# takiuino-m18-routed-smashed.net
KiCad netlist of a schematic drawn in EAGLE
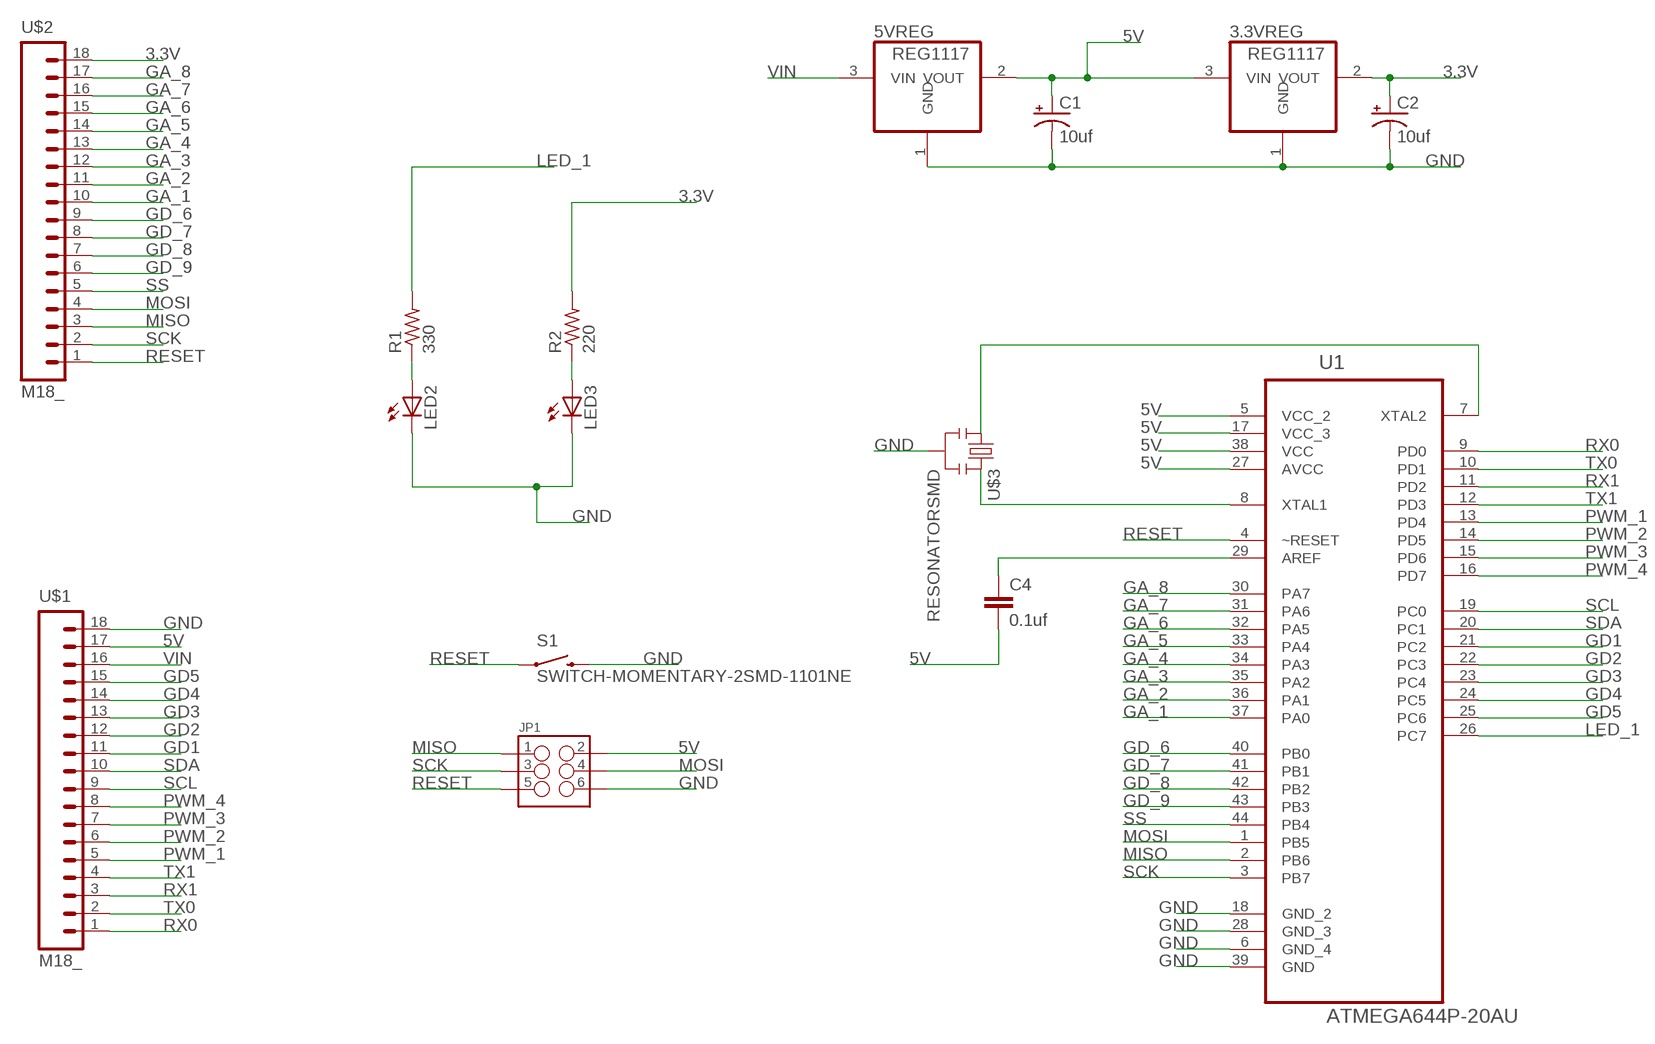
[diagram p0: schematic, sheet 1]

(export (version "E")
  (design (tool "Eeschema 10.0.6"))
  (components
    (comp (ref "3.3VREG")
      (value "REG1117")
      (footprint "eagle-import:SOT223")
      (libsource (lib "eagle-import") (part "REG1117"))
    )
    (comp (ref "5VREG")
      (value "REG1117")
      (footprint "eagle-import:SOT223")
      (libsource (lib "eagle-import") (part "REG1117"))
    )
    (comp (ref "C1")
      (value "10uf")
      (footprint "eagle-import:EIA3216")
      (libsource (lib "eagle-import") (part "CAP_POL1206"))
    )
    (comp (ref "C2")
      (value "10uf")
      (footprint "eagle-import:EIA3216")
      (libsource (lib "eagle-import") (part "CAP_POL1206"))
    )
    (comp (ref "C4")
      (value "0.1uf")
      (footprint "eagle-import:0603-CAP")
      (libsource (lib "eagle-import") (part "CAP0603-CAP"))
    )
    (comp (ref "JP1")
      (value "M03X2NO_SILK")
      (footprint "eagle-import:2X3-NS")
      (libsource (lib "eagle-import") (part "M03X2NO_SILK"))
    )
    (comp (ref "LED2")
      (value "LEDCHIP-LED0603")
      (footprint "eagle-import:CHIP-LED0603")
      (libsource (lib "eagle-import") (part "LEDCHIP-LED0603"))
    )
    (comp (ref "LED3")
      (value "LEDCHIP-LED0603")
      (footprint "eagle-import:CHIP-LED0603")
      (libsource (lib "eagle-import") (part "LEDCHIP-LED0603"))
    )
    (comp (ref "R1")
      (value "330")
      (footprint "eagle-import:R0603")
      (libsource (lib "eagle-import") (part "R-US_R0603"))
    )
    (comp (ref "R2")
      (value "220")
      (footprint "eagle-import:R0603")
      (libsource (lib "eagle-import") (part "R-US_R0603"))
    )
    (comp (ref "S1")
      (value "SWITCH-MOMENTARY-2SMD-1101NE")
      (footprint "eagle-import:TACTILE-SWITCH-1101NE")
      (libsource (lib "eagle-import") (part "SWITCH-MOMENTARY-2SMD-1101NE"))
    )
    (comp (ref "U$1")
      (value "M18_")
      (footprint "eagle-import:1X18")
      (libsource (lib "eagle-import") (part "M18_"))
    )
    (comp (ref "U$2")
      (value "M18_")
      (footprint "eagle-import:1X18")
      (libsource (lib "eagle-import") (part "M18_"))
    )
    (comp (ref "U$3")
      (value "RESONATORSMD")
      (footprint "eagle-import:RESONATOR-SMD")
      (libsource (lib "eagle-import") (part "RESONATORSMD"))
    )
    (comp (ref "U1")
      (value "ATMEGA644P-20AU")
      (footprint "eagle-import:QFP80P1200X1200X120-44N")
      (libsource (lib "eagle-import") (part "ATMEGA644P-20AU"))
    )
  )
  (nets
    (net (code "1") (name "/3.3V") (class "Default")
      (node (ref "3.3VREG") (pin "2") (pinfunction "VOUT_2") (pintype "output"))
      (node (ref "C2") (pin "A") (pinfunction "+_A") (pintype "passive"))
      (node (ref "R2") (pin "2") (pinfunction "2_2") (pintype "passive"))
      (node (ref "U$2") (pin "18") (pinfunction "18_18") (pintype "passive"))
    )
    (net (code "2") (name "/5V") (class "Default")
      (node (ref "3.3VREG") (pin "3") (pinfunction "VIN_3") (pintype "input"))
      (node (ref "5VREG") (pin "2") (pinfunction "VOUT_2") (pintype "output"))
      (node (ref "C1") (pin "A") (pinfunction "+_A") (pintype "passive"))
      (node (ref "C4") (pin "2") (pinfunction "2_2") (pintype "passive"))
      (node (ref "JP1") (pin "2") (pinfunction "2_2") (pintype "bidirectional"))
      (node (ref "U$1") (pin "17") (pinfunction "17_17") (pintype "passive"))
      (node (ref "U1") (pin "17") (pinfunction "VCC_3_17") (pintype "power_in"))
      (node (ref "U1") (pin "27") (pinfunction "AVCC_27") (pintype "power_in"))
      (node (ref "U1") (pin "38") (pinfunction "VCC_38") (pintype "power_in"))
      (node (ref "U1") (pin "5") (pinfunction "VCC_2_5") (pintype "power_in"))
    )
    (net (code "3") (name "/GA_1") (class "Default")
      (node (ref "U$2") (pin "10") (pinfunction "10_10") (pintype "passive"))
      (node (ref "U1") (pin "37") (pinfunction "PA0_37") (pintype "bidirectional"))
    )
    (net (code "4") (name "/GA_2") (class "Default")
      (node (ref "U$2") (pin "11") (pinfunction "11_11") (pintype "passive"))
      (node (ref "U1") (pin "36") (pinfunction "PA1_36") (pintype "bidirectional"))
    )
    (net (code "5") (name "/GA_3") (class "Default")
      (node (ref "U$2") (pin "12") (pinfunction "12_12") (pintype "passive"))
      (node (ref "U1") (pin "35") (pinfunction "PA2_35") (pintype "bidirectional"))
    )
    (net (code "6") (name "/GA_4") (class "Default")
      (node (ref "U$2") (pin "13") (pinfunction "13_13") (pintype "passive"))
      (node (ref "U1") (pin "34") (pinfunction "PA3_34") (pintype "bidirectional"))
    )
    (net (code "7") (name "/GA_5") (class "Default")
      (node (ref "U$2") (pin "14") (pinfunction "14_14") (pintype "passive"))
      (node (ref "U1") (pin "33") (pinfunction "PA4_33") (pintype "bidirectional"))
    )
    (net (code "8") (name "/GA_6") (class "Default")
      (node (ref "U$2") (pin "15") (pinfunction "15_15") (pintype "passive"))
      (node (ref "U1") (pin "32") (pinfunction "PA5_32") (pintype "bidirectional"))
    )
    (net (code "9") (name "/GA_7") (class "Default")
      (node (ref "U$2") (pin "16") (pinfunction "16_16") (pintype "passive"))
      (node (ref "U1") (pin "31") (pinfunction "PA6_31") (pintype "bidirectional"))
    )
    (net (code "10") (name "/GA_8") (class "Default")
      (node (ref "U$2") (pin "17") (pinfunction "17_17") (pintype "passive"))
      (node (ref "U1") (pin "30") (pinfunction "PA7_30") (pintype "bidirectional"))
    )
    (net (code "11") (name "/GD1") (class "Default")
      (node (ref "U$1") (pin "11") (pinfunction "11_11") (pintype "passive"))
      (node (ref "U1") (pin "21") (pinfunction "PC2_21") (pintype "bidirectional"))
    )
    (net (code "12") (name "/GD2") (class "Default")
      (node (ref "U$1") (pin "12") (pinfunction "12_12") (pintype "passive"))
      (node (ref "U1") (pin "22") (pinfunction "PC3_22") (pintype "bidirectional"))
    )
    (net (code "13") (name "/GD3") (class "Default")
      (node (ref "U$1") (pin "13") (pinfunction "13_13") (pintype "passive"))
      (node (ref "U1") (pin "23") (pinfunction "PC4_23") (pintype "bidirectional"))
    )
    (net (code "14") (name "/GD4") (class "Default")
      (node (ref "U$1") (pin "14") (pinfunction "14_14") (pintype "passive"))
      (node (ref "U1") (pin "24") (pinfunction "PC5_24") (pintype "bidirectional"))
    )
    (net (code "15") (name "/GD5") (class "Default")
      (node (ref "U$1") (pin "15") (pinfunction "15_15") (pintype "passive"))
      (node (ref "U1") (pin "25") (pinfunction "PC6_25") (pintype "bidirectional"))
    )
    (net (code "16") (name "/GD_6") (class "Default")
      (node (ref "U$2") (pin "9") (pinfunction "9_9") (pintype "passive"))
      (node (ref "U1") (pin "40") (pinfunction "PB0_40") (pintype "bidirectional"))
    )
    (net (code "17") (name "/GD_7") (class "Default")
      (node (ref "U$2") (pin "8") (pinfunction "8_8") (pintype "passive"))
      (node (ref "U1") (pin "41") (pinfunction "PB1_41") (pintype "bidirectional"))
    )
    (net (code "18") (name "/GD_8") (class "Default")
      (node (ref "U$2") (pin "7") (pinfunction "7_7") (pintype "passive"))
      (node (ref "U1") (pin "42") (pinfunction "PB2_42") (pintype "bidirectional"))
    )
    (net (code "19") (name "/GD_9") (class "Default")
      (node (ref "U$2") (pin "6") (pinfunction "6_6") (pintype "passive"))
      (node (ref "U1") (pin "43") (pinfunction "PB3_43") (pintype "bidirectional"))
    )
    (net (code "20") (name "/GND") (class "Default")
      (node (ref "3.3VREG") (pin "1") (pinfunction "GND_1") (pintype "power_in"))
      (node (ref "5VREG") (pin "1") (pinfunction "GND_1") (pintype "power_in"))
      (node (ref "C1") (pin "C") (pinfunction "-_C") (pintype "passive"))
      (node (ref "C2") (pin "C") (pinfunction "-_C") (pintype "passive"))
      (node (ref "JP1") (pin "6") (pinfunction "6_6") (pintype "bidirectional"))
      (node (ref "LED2") (pin "C") (pinfunction "C_C") (pintype "passive"))
      (node (ref "LED3") (pin "C") (pinfunction "C_C") (pintype "passive"))
      (node (ref "S1") (pin "2") (pinfunction "2_2") (pintype "passive"))
      (node (ref "U$1") (pin "18") (pinfunction "18_18") (pintype "passive"))
      (node (ref "U$3") (pin "2") (pinfunction "2_2") (pintype "passive"))
      (node (ref "U1") (pin "18") (pinfunction "GND_2_18") (pintype "passive"))
      (node (ref "U1") (pin "28") (pinfunction "GND_3_28") (pintype "passive"))
      (node (ref "U1") (pin "39") (pinfunction "GND_39") (pintype "passive"))
      (node (ref "U1") (pin "6") (pinfunction "GND_4_6") (pintype "passive"))
    )
    (net (code "21") (name "/LED_1") (class "Default")
      (node (ref "R1") (pin "2") (pinfunction "2_2") (pintype "passive"))
      (node (ref "U1") (pin "26") (pinfunction "PC7_26") (pintype "bidirectional"))
    )
    (net (code "22") (name "/MISO") (class "Default")
      (node (ref "JP1") (pin "1") (pinfunction "1_1") (pintype "bidirectional"))
      (node (ref "U$2") (pin "3") (pinfunction "3_3") (pintype "passive"))
      (node (ref "U1") (pin "2") (pinfunction "PB6_2") (pintype "bidirectional"))
    )
    (net (code "23") (name "/MOSI") (class "Default")
      (node (ref "JP1") (pin "4") (pinfunction "4_4") (pintype "bidirectional"))
      (node (ref "U$2") (pin "4") (pinfunction "4_4") (pintype "passive"))
      (node (ref "U1") (pin "1") (pinfunction "PB5_1") (pintype "bidirectional"))
    )
    (net (code "24") (name "/PWM_1") (class "Default")
      (node (ref "U$1") (pin "5") (pinfunction "5_5") (pintype "passive"))
      (node (ref "U1") (pin "13") (pinfunction "PD4_13") (pintype "bidirectional"))
    )
    (net (code "25") (name "/PWM_2") (class "Default")
      (node (ref "U$1") (pin "6") (pinfunction "6_6") (pintype "passive"))
      (node (ref "U1") (pin "14") (pinfunction "PD5_14") (pintype "bidirectional"))
    )
    (net (code "26") (name "/PWM_3") (class "Default")
      (node (ref "U$1") (pin "7") (pinfunction "7_7") (pintype "passive"))
      (node (ref "U1") (pin "15") (pinfunction "PD6_15") (pintype "bidirectional"))
    )
    (net (code "27") (name "/PWM_4") (class "Default")
      (node (ref "U$1") (pin "8") (pinfunction "8_8") (pintype "passive"))
      (node (ref "U1") (pin "16") (pinfunction "PD7_16") (pintype "bidirectional"))
    )
    (net (code "28") (name "/RESET") (class "Default")
      (node (ref "JP1") (pin "5") (pinfunction "5_5") (pintype "bidirectional"))
      (node (ref "S1") (pin "1") (pinfunction "1_1") (pintype "passive"))
      (node (ref "U$2") (pin "1") (pinfunction "1_1") (pintype "passive"))
      (node (ref "U1") (pin "4") (pinfunction "~{RESET}_4") (pintype "input"))
    )
    (net (code "29") (name "/RX0") (class "Default")
      (node (ref "U$1") (pin "1") (pinfunction "1_1") (pintype "passive"))
      (node (ref "U1") (pin "9") (pinfunction "PD0_9") (pintype "bidirectional"))
    )
    (net (code "30") (name "/RX1") (class "Default")
      (node (ref "U$1") (pin "3") (pinfunction "3_3") (pintype "passive"))
      (node (ref "U1") (pin "11") (pinfunction "PD2_11") (pintype "bidirectional"))
    )
    (net (code "31") (name "/SCK") (class "Default")
      (node (ref "JP1") (pin "3") (pinfunction "3_3") (pintype "bidirectional"))
      (node (ref "U$2") (pin "2") (pinfunction "2_2") (pintype "passive"))
      (node (ref "U1") (pin "3") (pinfunction "PB7_3") (pintype "bidirectional"))
    )
    (net (code "32") (name "/SCL") (class "Default")
      (node (ref "U$1") (pin "9") (pinfunction "9_9") (pintype "passive"))
      (node (ref "U1") (pin "19") (pinfunction "PC0_19") (pintype "bidirectional"))
    )
    (net (code "33") (name "/SDA") (class "Default")
      (node (ref "U$1") (pin "10") (pinfunction "10_10") (pintype "passive"))
      (node (ref "U1") (pin "20") (pinfunction "PC1_20") (pintype "bidirectional"))
    )
    (net (code "34") (name "/SS") (class "Default")
      (node (ref "U$2") (pin "5") (pinfunction "5_5") (pintype "passive"))
      (node (ref "U1") (pin "44") (pinfunction "PB4_44") (pintype "bidirectional"))
    )
    (net (code "35") (name "/TX0") (class "Default")
      (node (ref "U$1") (pin "2") (pinfunction "2_2") (pintype "passive"))
      (node (ref "U1") (pin "10") (pinfunction "PD1_10") (pintype "bidirectional"))
    )
    (net (code "36") (name "/TX1") (class "Default")
      (node (ref "U$1") (pin "4") (pinfunction "4_4") (pintype "passive"))
      (node (ref "U1") (pin "12") (pinfunction "PD3_12") (pintype "bidirectional"))
    )
    (net (code "37") (name "/VIN") (class "Default")
      (node (ref "5VREG") (pin "3") (pinfunction "VIN_3") (pintype "input"))
      (node (ref "U$1") (pin "16") (pinfunction "16_16") (pintype "passive"))
    )
    (net (code "38") (name "Net-(LED2-PadA)") (class "Default")
      (node (ref "LED2") (pin "A") (pinfunction "A_A") (pintype "passive"))
      (node (ref "R1") (pin "1") (pinfunction "1_1") (pintype "passive"))
    )
    (net (code "39") (name "Net-(LED3-PadA)") (class "Default")
      (node (ref "LED3") (pin "A") (pinfunction "A_A") (pintype "passive"))
      (node (ref "R2") (pin "1") (pinfunction "1_1") (pintype "passive"))
    )
    (net (code "40") (name "Net-(U1-AREF)") (class "Default")
      (node (ref "C4") (pin "1") (pinfunction "1_1") (pintype "passive"))
      (node (ref "U1") (pin "29") (pinfunction "AREF_29") (pintype "input"))
    )
    (net (code "41") (name "Net-(U1-XTAL1)") (class "Default")
      (node (ref "U$3") (pin "3") (pinfunction "3_3") (pintype "passive"))
      (node (ref "U1") (pin "8") (pinfunction "XTAL1_8") (pintype "input"))
    )
    (net (code "42") (name "Net-(U1-XTAL2)") (class "Default")
      (node (ref "U$3") (pin "1") (pinfunction "1_1") (pintype "passive"))
      (node (ref "U1") (pin "7") (pinfunction "XTAL2_7") (pintype "output"))
    )
  )
)
